# Channel.net
KiCad netlist of a schematic drawn in Altium Designer
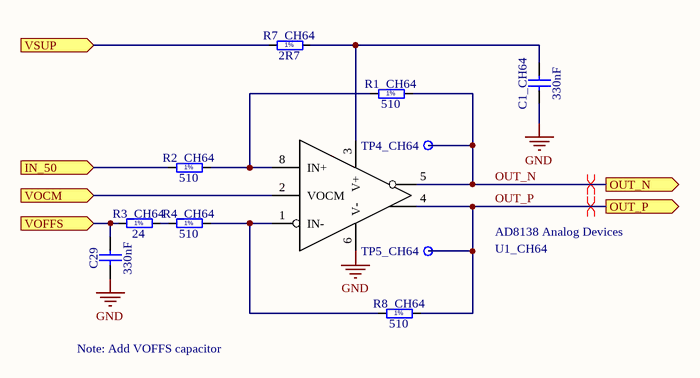
[diagram p0: Channel.SchDoc]

(export (version "E")
  (design (tool "Eeschema 10.0.6"))
  (components
    (comp (ref "C1_CH64")
      (value "330nF")
      (footprint "CAPC2012X135N")
      (description "Non-polarised capacitor")
      (fields
        (field (name "PART NUMBER") "CC0805_330NF_16V_10%_X7R")
        (field (name "VOLTAGE") "16V")
        (field (name "AUTHOR") "CERN DEM JLC")
      )
      (libsource (lib "Capacitors") (part "Capacitor - non polarized"))
    )
    (comp (ref "C29")
      (value "330nF")
      (footprint "CAPC2012X135N")
      (description "Non-polarised capacitor")
      (fields
        (field (name "PART NUMBER") "CC0805_330NF_16V_10%_X7R")
        (field (name "VOLTAGE") "16V")
        (field (name "AUTHOR") "CERN DEM JLC")
      )
      (libsource (lib "Capacitors") (part "Capacitor - non polarized"))
    )
    (comp (ref "R1_CH64")
      (value "510")
      (footprint "RESC2012X60N")
      (description "Resistor - 1%")
      (fields
        (field (name "PART NUMBER") "R0805_510R_1%_0.125W_100PPM")
        (field (name "POWER") "0.125W")
        (field (name "AUTHOR") "CERN DEM JLC")
      )
      (libsource (lib "Resistors") (part "Resistor - 1%"))
    )
    (comp (ref "R2_CH64")
      (value "510")
      (footprint "RESC2012X60N")
      (description "Resistor - 1%")
      (fields
        (field (name "PART NUMBER") "R0805_510R_1%_0.125W_100PPM")
        (field (name "POWER") "0.125W")
        (field (name "AUTHOR") "CERN DEM JLC")
      )
      (libsource (lib "Resistors") (part "Resistor - 1%"))
    )
    (comp (ref "R3_CH64")
      (value "24")
      (footprint "RESC2012X60N")
      (description "Resistor - 1%")
      (fields
        (field (name "PART NUMBER") "R0805_24R_1%_0.125W_100PPM")
        (field (name "POWER") "0.125W")
        (field (name "AUTHOR") "CERN DEM JLC")
      )
      (libsource (lib "Resistors") (part "Resistor - 1%"))
    )
    (comp (ref "R4_CH64")
      (value "510")
      (footprint "RESC2012X60N")
      (description "Resistor - 1%")
      (fields
        (field (name "PART NUMBER") "R0805_510R_1%_0.125W_100PPM")
        (field (name "POWER") "0.125W")
        (field (name "AUTHOR") "CERN DEM JLC")
      )
      (libsource (lib "Resistors") (part "Resistor - 1%"))
    )
    (comp (ref "R7_CH64")
      (value "2R7")
      (footprint "RESC2012X60N")
      (description "Resistor - 1%")
      (fields
        (field (name "PART NUMBER") "R0805_2R7_1%_0.125W_200PPM")
        (field (name "POWER") "0.125W")
        (field (name "AUTHOR") "CERN DEM JLC")
      )
      (libsource (lib "Resistors") (part "Resistor - 1%"))
    )
    (comp (ref "R8_CH64")
      (value "510")
      (footprint "RESC2012X60N")
      (description "Resistor - 1%")
      (fields
        (field (name "PART NUMBER") "R0805_510R_1%_0.125W_100PPM")
        (field (name "POWER") "0.125W")
        (field (name "AUTHOR") "CERN DEM JLC")
      )
      (libsource (lib "Resistors") (part "Resistor - 1%"))
    )
    (comp (ref "TP4_CH64")
      (value "Test Point")
      (footprint "Testpoint")
      (fields
        (field (name "PART NUMBER") "VERO_20-313145")
        (field (name "MANUFACTURER") "VERO TECHNOLOGIES")
        (field (name "MANUFACTURER PART NUMBER") "20-313145")
        (field (name "AUTHOR") "CERN DEM JLC")
      )
      (libsource (lib "Connectors") (part "Test Point"))
    )
    (comp (ref "TP5_CH64")
      (value "Test Point")
      (footprint "Testpoint")
      (fields
        (field (name "PART NUMBER") "VERO_20-313145")
        (field (name "MANUFACTURER") "VERO TECHNOLOGIES")
        (field (name "MANUFACTURER PART NUMBER") "20-313145")
        (field (name "AUTHOR") "CERN DEM JLC")
      )
      (libsource (lib "Connectors") (part "Test Point"))
    )
    (comp (ref "U1_CH64")
      (value "AD8138 Analog Devices")
      (footprint "SOIC127P600X175-8N")
      (fields (field (name "MANUFACTURER") "Analog Devices"))
      (libsource (lib "Additional") (part "AD8138"))
    )
  )
  (nets
    (net (code "1") (name "/IN_50") (class "Default")
      (node (ref "R2_CH64") (pin "1") (pinfunction "1_1") (pintype "passive"))
    )
    (net (code "2") (name "/OUT_N") (class "Default")
      (node (ref "R1_CH64") (pin "2") (pinfunction "2_2") (pintype "passive"))
      (node (ref "TP4_CH64") (pin "1") (pinfunction "1_1") (pintype "bidirectional"))
      (node (ref "U1_CH64") (pin "5") (pinfunction "OUT-_5") (pintype "passive"))
    )
    (net (code "3") (name "/OUT_P") (class "Default")
      (node (ref "R8_CH64") (pin "2") (pinfunction "2_2") (pintype "passive"))
      (node (ref "TP5_CH64") (pin "1") (pinfunction "1_1") (pintype "bidirectional"))
      (node (ref "U1_CH64") (pin "4") (pinfunction "OUT+_4") (pintype "passive"))
    )
    (net (code "4") (name "/VOCM") (class "Default")
      (node (ref "U1_CH64") (pin "2") (pinfunction "VOCM_2") (pintype "passive"))
    )
    (net (code "5") (name "/VOFFS") (class "Default")
      (node (ref "C29") (pin "2") (pinfunction "2_2") (pintype "passive"))
      (node (ref "R3_CH64") (pin "1") (pinfunction "1_1") (pintype "passive"))
    )
    (net (code "6") (name "/VSUP") (class "Default")
      (node (ref "R7_CH64") (pin "1") (pinfunction "1_1") (pintype "passive"))
    )
    (net (code "7") (name "GND") (class "Default")
      (node (ref "C1_CH64") (pin "1") (pinfunction "1_1") (pintype "passive"))
      (node (ref "C29") (pin "1") (pinfunction "1_1") (pintype "passive"))
      (node (ref "U1_CH64") (pin "6") (pinfunction "V-_6") (pintype "passive"))
    )
    (net (code "8") (name "Net-(R3_CH64-Pad2)") (class "Default")
      (node (ref "R3_CH64") (pin "2") (pinfunction "2_2") (pintype "passive"))
      (node (ref "R4_CH64") (pin "1") (pinfunction "1_1") (pintype "passive"))
    )
    (net (code "9") (name "Net-(U1_CH64-IN+)") (class "Default")
      (node (ref "R1_CH64") (pin "1") (pinfunction "1_1") (pintype "passive"))
      (node (ref "R2_CH64") (pin "2") (pinfunction "2_2") (pintype "passive"))
      (node (ref "U1_CH64") (pin "8") (pinfunction "IN+_8") (pintype "passive"))
    )
    (net (code "10") (name "Net-(U1_CH64-IN-)") (class "Default")
      (node (ref "R4_CH64") (pin "2") (pinfunction "2_2") (pintype "passive"))
      (node (ref "R8_CH64") (pin "1") (pinfunction "1_1") (pintype "passive"))
      (node (ref "U1_CH64") (pin "1") (pinfunction "IN-_1") (pintype "passive"))
    )
    (net (code "11") (name "Net-(U1_CH64-V+)") (class "Default")
      (node (ref "C1_CH64") (pin "2") (pinfunction "2_2") (pintype "passive"))
      (node (ref "R7_CH64") (pin "2") (pinfunction "2_2") (pintype "passive"))
      (node (ref "U1_CH64") (pin "3") (pinfunction "V+_3") (pintype "passive"))
    )
  )
)
